# capacitive_touch.net
KiCad netlist of a schematic drawn in EAGLE
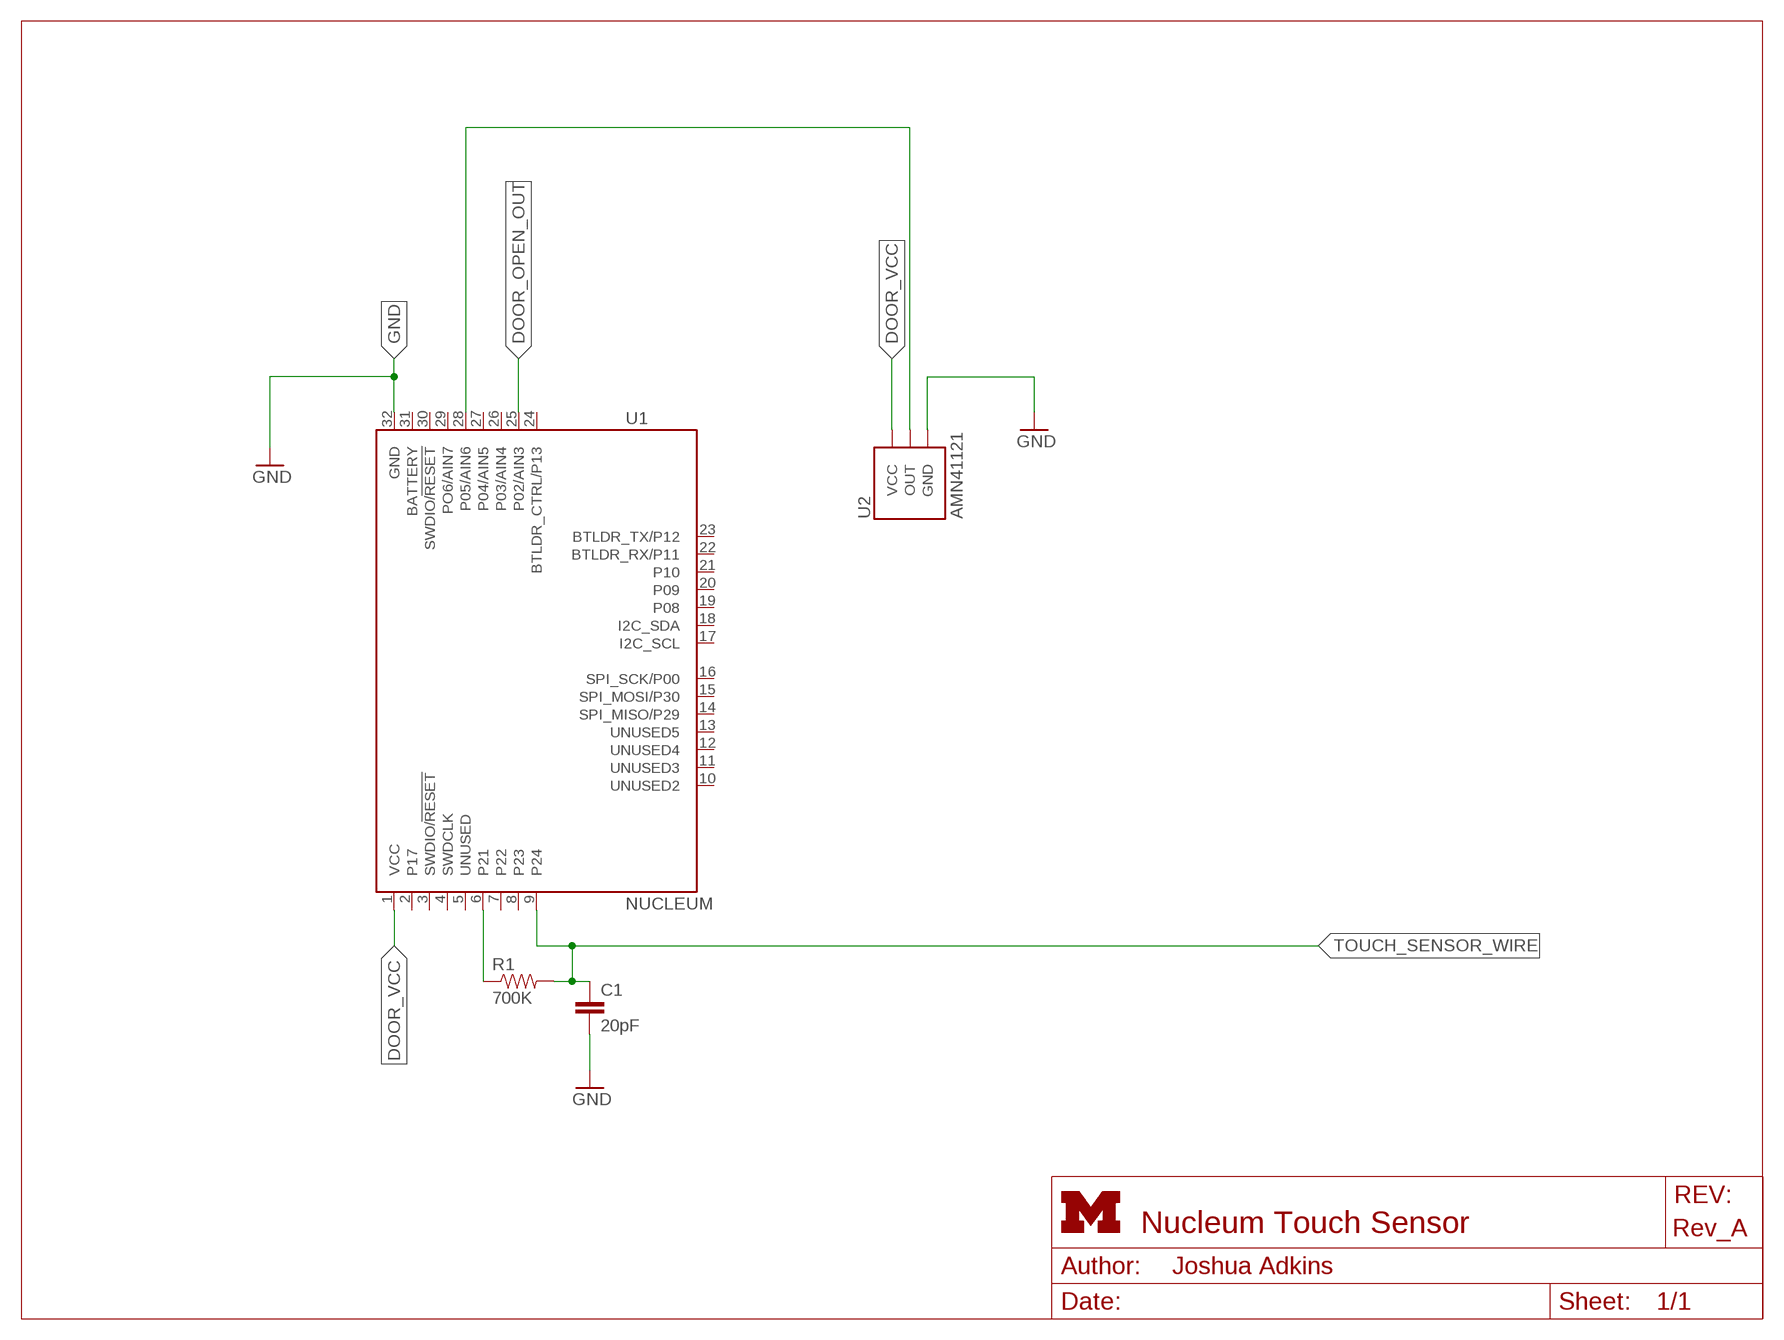
[diagram p0: schematic, sheet 1]

(export (version "E")
  (design (tool "Eeschema 10.0.6"))
  (components
    (comp (ref "C1")
      (value "20pF")
      (footprint "eagle-import:1206")
      (libsource (lib "eagle-import") (part "CAP1206"))
    )
    (comp (ref "R1")
      (value "700K")
      (footprint "eagle-import:0603-RES")
      (libsource (lib "eagle-import") (part "RESISTOR"))
    )
    (comp (ref "U1")
      (value "NUCLEUM")
      (footprint "eagle-import:NUCLEUM")
      (libsource (lib "eagle-import") (part "NUCLEUM"))
    )
    (comp (ref "U2")
      (value "AMN41121")
      (footprint "eagle-import:AMN2")
      (libsource (lib "eagle-import") (part "AMN41121"))
    )
  )
  (nets
    (net (code "1") (name "DOOR_OPEN_OUT") (class "Default")
      (node (ref "U1") (pin "25") (pinfunction "P02/AIN3_25") (pintype "bidirectional"))
    )
    (net (code "2") (name "DOOR_VCC") (class "Default")
      (node (ref "U1") (pin "1") (pinfunction "VCC_1") (pintype "bidirectional"))
      (node (ref "U2") (pin "VCC") (pinfunction "VCC_VCC") (pintype "bidirectional"))
    )
    (net (code "3") (name "GND") (class "Default")
      (node (ref "C1") (pin "2") (pinfunction "2_2") (pintype "passive"))
      (node (ref "U1") (pin "32") (pinfunction "GND_32") (pintype "bidirectional"))
      (node (ref "U2") (pin "GND") (pinfunction "GND_GND") (pintype "bidirectional"))
    )
    (net (code "4") (name "Net-(U1-P05{slash}AIN6)") (class "Default")
      (node (ref "U1") (pin "28") (pinfunction "P05/AIN6_28") (pintype "bidirectional"))
      (node (ref "U2") (pin "OUT") (pinfunction "OUT_OUT") (pintype "bidirectional"))
    )
    (net (code "5") (name "Net-(U1-P21)") (class "Default")
      (node (ref "R1") (pin "1") (pinfunction "1_1") (pintype "passive"))
      (node (ref "U1") (pin "6") (pinfunction "P21_6") (pintype "bidirectional"))
    )
    (net (code "6") (name "TOUCH_SENSOR_WIRE") (class "Default")
      (node (ref "C1") (pin "1") (pinfunction "1_1") (pintype "passive"))
      (node (ref "R1") (pin "2") (pinfunction "2_2") (pintype "passive"))
      (node (ref "U1") (pin "9") (pinfunction "P24_9") (pintype "bidirectional"))
    )
    (net (code "7") (name "unconnected-(U1-BATTERY-Pad31)") (class "Default")
      (node (ref "U1") (pin "31") (pinfunction "BATTERY_31") (pintype "bidirectional"))
    )
    (net (code "8") (name "unconnected-(U1-BTLDR_CTRL{slash}P13-Pad24)") (class "Default")
      (node (ref "U1") (pin "24") (pinfunction "BTLDR_CTRL/P13_24") (pintype "bidirectional"))
    )
    (net (code "9") (name "unconnected-(U1-BTLDR_RX{slash}P11-Pad22)") (class "Default")
      (node (ref "U1") (pin "22") (pinfunction "BTLDR_RX/P11_22") (pintype "bidirectional"))
    )
    (net (code "10") (name "unconnected-(U1-BTLDR_TX{slash}P12-Pad23)") (class "Default")
      (node (ref "U1") (pin "23") (pinfunction "BTLDR_TX/P12_23") (pintype "bidirectional"))
    )
    (net (code "11") (name "unconnected-(U1-I2C_SCL-Pad17)") (class "Default")
      (node (ref "U1") (pin "17") (pinfunction "I2C_SCL_17") (pintype "bidirectional"))
    )
    (net (code "12") (name "unconnected-(U1-I2C_SDA-Pad18)") (class "Default")
      (node (ref "U1") (pin "18") (pinfunction "I2C_SDA_18") (pintype "bidirectional"))
    )
    (net (code "13") (name "unconnected-(U1-P03{slash}AIN4-Pad26)") (class "Default")
      (node (ref "U1") (pin "26") (pinfunction "P03/AIN4_26") (pintype "bidirectional"))
    )
    (net (code "14") (name "unconnected-(U1-P04{slash}AIN5-Pad27)") (class "Default")
      (node (ref "U1") (pin "27") (pinfunction "P04/AIN5_27") (pintype "bidirectional"))
    )
    (net (code "15") (name "unconnected-(U1-P08-Pad19)") (class "Default")
      (node (ref "U1") (pin "19") (pinfunction "P08_19") (pintype "bidirectional"))
    )
    (net (code "16") (name "unconnected-(U1-P09-Pad20)") (class "Default")
      (node (ref "U1") (pin "20") (pinfunction "P09_20") (pintype "bidirectional"))
    )
    (net (code "17") (name "unconnected-(U1-P10-Pad21)") (class "Default")
      (node (ref "U1") (pin "21") (pinfunction "P10_21") (pintype "bidirectional"))
    )
    (net (code "18") (name "unconnected-(U1-P17-Pad2)") (class "Default")
      (node (ref "U1") (pin "2") (pinfunction "P17_2") (pintype "bidirectional"))
    )
    (net (code "19") (name "unconnected-(U1-P22-Pad7)") (class "Default")
      (node (ref "U1") (pin "7") (pinfunction "P22_7") (pintype "bidirectional"))
    )
    (net (code "20") (name "unconnected-(U1-P23-Pad8)") (class "Default")
      (node (ref "U1") (pin "8") (pinfunction "P23_8") (pintype "bidirectional"))
    )
    (net (code "21") (name "unconnected-(U1-PO6{slash}AIN7-Pad29)") (class "Default")
      (node (ref "U1") (pin "29") (pinfunction "PO6/AIN7_29") (pintype "bidirectional"))
    )
    (net (code "22") (name "unconnected-(U1-SPI_MISO{slash}P29-Pad14)") (class "Default")
      (node (ref "U1") (pin "14") (pinfunction "SPI_MISO/P29_14") (pintype "bidirectional"))
    )
    (net (code "23") (name "unconnected-(U1-SPI_MOSI{slash}P30-Pad15)") (class "Default")
      (node (ref "U1") (pin "15") (pinfunction "SPI_MOSI/P30_15") (pintype "bidirectional"))
    )
    (net (code "24") (name "unconnected-(U1-SPI_SCK{slash}P00-Pad16)") (class "Default")
      (node (ref "U1") (pin "16") (pinfunction "SPI_SCK/P00_16") (pintype "bidirectional"))
    )
    (net (code "25") (name "unconnected-(U1-SWDCLK-Pad4)") (class "Default")
      (node (ref "U1") (pin "4") (pinfunction "SWDCLK_4") (pintype "bidirectional"))
    )
    (net (code "26") (name "unconnected-(U1-SWDIO{slash}~{RESET}-Pad3)") (class "Default")
      (node (ref "U1") (pin "3") (pinfunction "SWDIO/~{RESET}_3") (pintype "bidirectional"))
    )
    (net (code "27") (name "unconnected-(U1-SWDIO{slash}~{RESET}-Pad30)") (class "Default")
      (node (ref "U1") (pin "30") (pinfunction "SWDIO/~{RESET}_30") (pintype "bidirectional"))
    )
    (net (code "28") (name "unconnected-(U1-UNUSED-Pad5)") (class "Default")
      (node (ref "U1") (pin "5") (pinfunction "UNUSED_5") (pintype "bidirectional"))
    )
    (net (code "29") (name "unconnected-(U1-UNUSED2-Pad10)") (class "Default")
      (node (ref "U1") (pin "10") (pinfunction "UNUSED2_10") (pintype "bidirectional"))
    )
    (net (code "30") (name "unconnected-(U1-UNUSED3-Pad11)") (class "Default")
      (node (ref "U1") (pin "11") (pinfunction "UNUSED3_11") (pintype "bidirectional"))
    )
    (net (code "31") (name "unconnected-(U1-UNUSED4-Pad12)") (class "Default")
      (node (ref "U1") (pin "12") (pinfunction "UNUSED4_12") (pintype "bidirectional"))
    )
    (net (code "32") (name "unconnected-(U1-UNUSED5-Pad13)") (class "Default")
      (node (ref "U1") (pin "13") (pinfunction "UNUSED5_13") (pintype "bidirectional"))
    )
  )
)
